# Adafruit_0_96in_160x80_TFT_Display.net
KiCad netlist of a schematic drawn in EAGLE
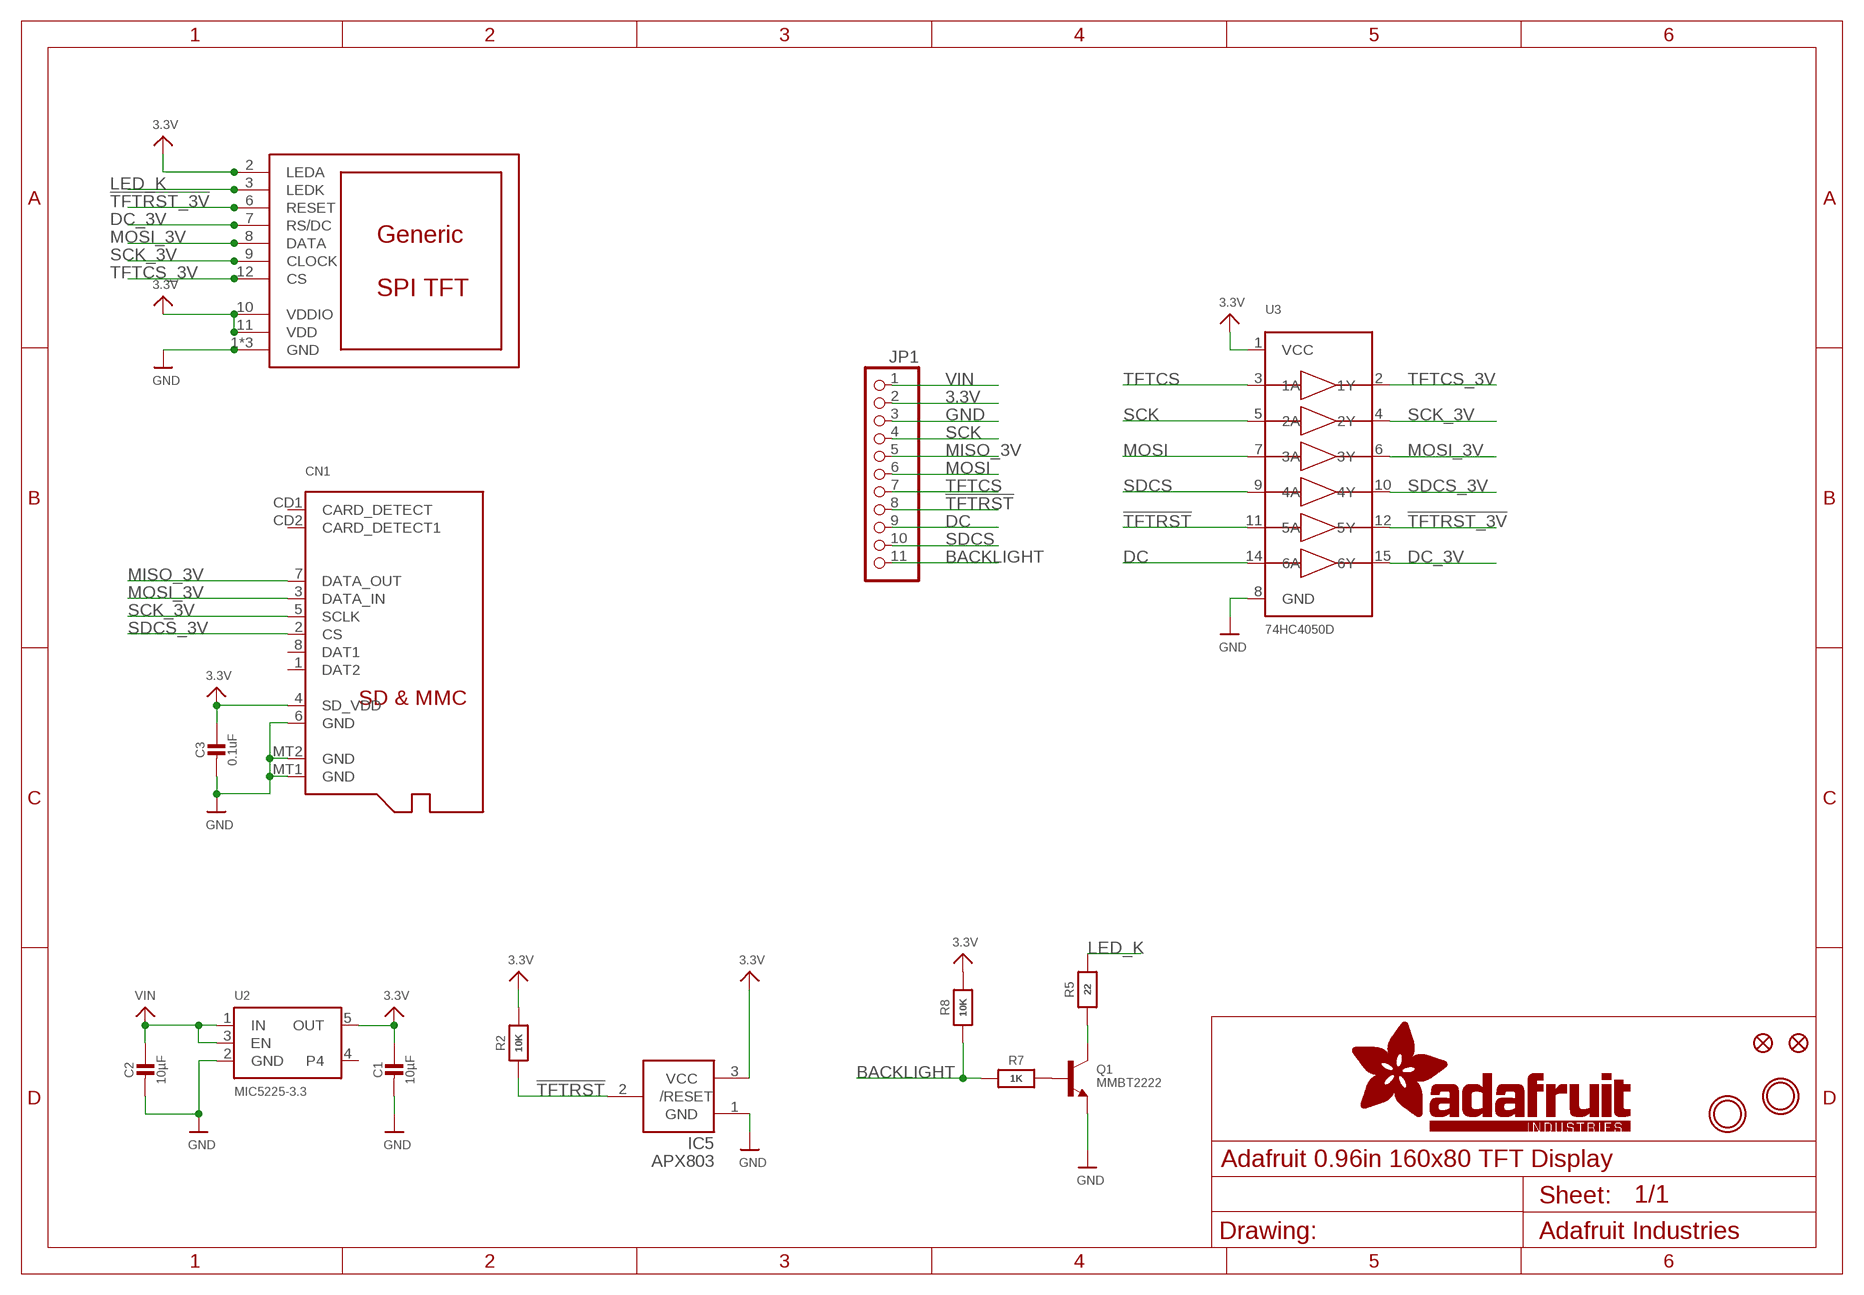
[diagram p0: schematic, sheet 1]

(export (version "E")
  (design (tool "Eeschema 10.0.6"))
  (components
    (comp (ref "C1")
      (value "10µF")
      (footprint "eagle-import:0805-NO")
      (libsource (lib "eagle-import") (part "CAP_CERAMIC0805-NOOUTLINE"))
    )
    (comp (ref "C2")
      (value "10µF")
      (footprint "eagle-import:0805-NO")
      (libsource (lib "eagle-import") (part "CAP_CERAMIC0805-NOOUTLINE"))
    )
    (comp (ref "C3")
      (value "0.1uF")
      (footprint "eagle-import:0805-NO")
      (libsource (lib "eagle-import") (part "CAP_CERAMIC0805-NOOUTLINE"))
    )
    (comp (ref "CN1")
      (value "MICROSD")
      (footprint "eagle-import:MICROSD")
      (libsource (lib "eagle-import") (part "MICROSD"))
    )
    (comp (ref "FID1")
      (value "FIDUCIAL_1MM")
      (footprint "eagle-import:FIDUCIAL_1MM")
      (libsource (lib "eagle-import") (part "FIDUCIAL_1MM"))
    )
    (comp (ref "FID2")
      (value "FIDUCIAL_1MM")
      (footprint "eagle-import:FIDUCIAL_1MM")
      (libsource (lib "eagle-import") (part "FIDUCIAL_1MM"))
    )
    (comp (ref "IC5")
      (value "APX803")
      (footprint "eagle-import:SOT23")
      (libsource (lib "eagle-import") (part "AXP083-SAG"))
    )
    (comp (ref "JP1")
      (value "HEADER-1X11")
      (footprint "eagle-import:1X11_ROUND")
      (libsource (lib "eagle-import") (part "HEADER-1X11"))
    )
    (comp (ref "Q1")
      (value "MMBT2222")
      (footprint "eagle-import:SOT23-WIDE")
      (libsource (lib "eagle-import") (part "TRANSISTOR_NPNWIDE"))
    )
    (comp (ref "R2")
      (value "10K")
      (footprint "eagle-import:0603-NO")
      (libsource (lib "eagle-import") (part "RESISTOR_0603_NOOUT"))
    )
    (comp (ref "R5")
      (value "22")
      (footprint "eagle-import:0603-NO")
      (libsource (lib "eagle-import") (part "RESISTOR_0603_NOOUT"))
    )
    (comp (ref "R7")
      (value "1K")
      (footprint "eagle-import:0603-NO")
      (libsource (lib "eagle-import") (part "RESISTOR_0603_NOOUT"))
    )
    (comp (ref "R8")
      (value "10K")
      (footprint "eagle-import:0603-NO")
      (libsource (lib "eagle-import") (part "RESISTOR_0603_NOOUT"))
    )
    (comp (ref "U$2")
      (value "DISP_LCD_0.9IN_160X80")
      (footprint "eagle-import:TFT_0.96IN_160X80")
      (libsource (lib "eagle-import") (part "DISP_LCD_0.9IN_160X80"))
    )
    (comp (ref "U$9")
      (value "MOUNTINGHOLE2.5")
      (footprint "eagle-import:MOUNTINGHOLE_2.5_PLATED")
      (libsource (lib "eagle-import") (part "MOUNTINGHOLE2.5"))
    )
    (comp (ref "U$10")
      (value "MOUNTINGHOLE2.5")
      (footprint "eagle-import:MOUNTINGHOLE_2.5_PLATED")
      (libsource (lib "eagle-import") (part "MOUNTINGHOLE2.5"))
    )
    (comp (ref "U2")
      (value "MIC5225-3.3")
      (footprint "eagle-import:SOT23-5")
      (libsource (lib "eagle-import") (part "VREG_SOT23-5"))
    )
    (comp (ref "U3")
      (value "74HC4050D")
      (footprint "eagle-import:SOIC16")
      (libsource (lib "eagle-import") (part "74HC4050D"))
    )
  )
  (nets
    (net (code "1") (name "/BACKLIGHT") (class "Default")
      (node (ref "JP1") (pin "11") (pinfunction "11_11") (pintype "passive"))
      (node (ref "R7") (pin "1") (pinfunction "1_1") (pintype "passive"))
      (node (ref "R8") (pin "1") (pinfunction "1_1") (pintype "passive"))
    )
    (net (code "2") (name "/DC") (class "Default")
      (node (ref "JP1") (pin "9") (pinfunction "9_9") (pintype "passive"))
      (node (ref "U3") (pin "14") (pinfunction "6A_14") (pintype "bidirectional"))
    )
    (net (code "3") (name "/DC_3V") (class "Default")
      (node (ref "U$2") (pin "7") (pinfunction "RS/DC_7") (pintype "input"))
      (node (ref "U3") (pin "15") (pinfunction "6Y_15") (pintype "bidirectional"))
    )
    (net (code "4") (name "/LED_K") (class "Default")
      (node (ref "R5") (pin "2") (pinfunction "2_2") (pintype "passive"))
      (node (ref "U$2") (pin "3") (pinfunction "LEDK_3") (pintype "input"))
    )
    (net (code "5") (name "/MISO_3V") (class "Default")
      (node (ref "CN1") (pin "7") (pinfunction "DATA_OUT_7") (pintype "output"))
      (node (ref "JP1") (pin "5") (pinfunction "5_5") (pintype "passive"))
    )
    (net (code "6") (name "/MOSI") (class "Default")
      (node (ref "JP1") (pin "6") (pinfunction "6_6") (pintype "passive"))
      (node (ref "U3") (pin "7") (pinfunction "3A_7") (pintype "bidirectional"))
    )
    (net (code "7") (name "/MOSI_3V") (class "Default")
      (node (ref "CN1") (pin "3") (pinfunction "DATA_IN_3") (pintype "input"))
      (node (ref "U$2") (pin "8") (pinfunction "DATA_8") (pintype "bidirectional"))
      (node (ref "U3") (pin "6") (pinfunction "3Y_6") (pintype "bidirectional"))
    )
    (net (code "8") (name "/SCK") (class "Default")
      (node (ref "JP1") (pin "4") (pinfunction "4_4") (pintype "passive"))
      (node (ref "U3") (pin "5") (pinfunction "2A_5") (pintype "bidirectional"))
    )
    (net (code "9") (name "/SCK_3V") (class "Default")
      (node (ref "CN1") (pin "5") (pinfunction "SCLK_5") (pintype "input"))
      (node (ref "U$2") (pin "9") (pinfunction "CLOCK_9") (pintype "input"))
      (node (ref "U3") (pin "4") (pinfunction "2Y_4") (pintype "bidirectional"))
    )
    (net (code "10") (name "/SDCS") (class "Default")
      (node (ref "JP1") (pin "10") (pinfunction "10_10") (pintype "passive"))
      (node (ref "U3") (pin "9") (pinfunction "4A_9") (pintype "bidirectional"))
    )
    (net (code "11") (name "/SDCS_3V") (class "Default")
      (node (ref "CN1") (pin "2") (pinfunction "CS_2") (pintype "input"))
      (node (ref "U3") (pin "10") (pinfunction "4Y_10") (pintype "bidirectional"))
    )
    (net (code "12") (name "/TFTCS") (class "Default")
      (node (ref "JP1") (pin "7") (pinfunction "7_7") (pintype "passive"))
      (node (ref "U3") (pin "3") (pinfunction "1A_3") (pintype "bidirectional"))
    )
    (net (code "13") (name "/TFTCS_3V") (class "Default")
      (node (ref "U$2") (pin "12") (pinfunction "CS_12") (pintype "input"))
      (node (ref "U3") (pin "2") (pinfunction "1Y_2") (pintype "bidirectional"))
    )
    (net (code "14") (name "/~{TFTRST_3V}") (class "Default")
      (node (ref "U$2") (pin "6") (pinfunction "RESET_6") (pintype "input"))
      (node (ref "U3") (pin "12") (pinfunction "5Y_12") (pintype "bidirectional"))
    )
    (net (code "15") (name "/~{TFTRST}") (class "Default")
      (node (ref "IC5") (pin "2") (pinfunction "/RESET_2") (pintype "output"))
      (node (ref "JP1") (pin "8") (pinfunction "8_8") (pintype "passive"))
      (node (ref "R2") (pin "1") (pinfunction "1_1") (pintype "passive"))
      (node (ref "U3") (pin "11") (pinfunction "5A_11") (pintype "bidirectional"))
    )
    (net (code "16") (name "3.3V") (class "Default")
      (node (ref "C1") (pin "1") (pinfunction "1_1") (pintype "passive"))
      (node (ref "C3") (pin "1") (pinfunction "1_1") (pintype "passive"))
      (node (ref "CN1") (pin "4") (pinfunction "SD_VDD_4") (pintype "power_in"))
      (node (ref "IC5") (pin "3") (pinfunction "VCC_3") (pintype "power_in"))
      (node (ref "JP1") (pin "2") (pinfunction "2_2") (pintype "passive"))
      (node (ref "R2") (pin "2") (pinfunction "2_2") (pintype "passive"))
      (node (ref "R8") (pin "2") (pinfunction "2_2") (pintype "passive"))
      (node (ref "U$2") (pin "10") (pinfunction "VDDIO_10") (pintype "power_in"))
      (node (ref "U$2") (pin "11") (pinfunction "VDD_11") (pintype "power_in"))
      (node (ref "U$2") (pin "2") (pinfunction "LEDA_2") (pintype "input"))
      (node (ref "U2") (pin "5") (pinfunction "OUT_5") (pintype "power_in"))
      (node (ref "U3") (pin "1") (pinfunction "VCC_1") (pintype "bidirectional"))
    )
    (net (code "17") (name "GND") (class "Default")
      (node (ref "C1") (pin "2") (pinfunction "2_2") (pintype "passive"))
      (node (ref "C2") (pin "2") (pinfunction "2_2") (pintype "passive"))
      (node (ref "C3") (pin "2") (pinfunction "2_2") (pintype "passive"))
      (node (ref "CN1") (pin "6") (pinfunction "GND_6") (pintype "power_in"))
      (node (ref "CN1") (pin "MT1") (pinfunction "GND_MT1") (pintype "power_in"))
      (node (ref "CN1") (pin "MT2") (pinfunction "GND_MT2") (pintype "power_in"))
      (node (ref "IC5") (pin "1") (pinfunction "GND_1") (pintype "power_in"))
      (node (ref "JP1") (pin "3") (pinfunction "3_3") (pintype "passive"))
      (node (ref "Q1") (pin "2") (pinfunction "E_2") (pintype "passive"))
      (node (ref "U$2") (pin "1") (pinfunction "GND_1") (pintype "power_in"))
      (node (ref "U$2") (pin "13") (pinfunction "GND_13") (pintype "power_in"))
      (node (ref "U$2") (pin "5") (pinfunction "GND_5") (pintype "power_in"))
      (node (ref "U2") (pin "2") (pinfunction "GND_2") (pintype "power_in"))
      (node (ref "U3") (pin "8") (pinfunction "GND_8") (pintype "bidirectional"))
    )
    (net (code "18") (name "Net-(Q1-B)") (class "Default")
      (node (ref "Q1") (pin "1") (pinfunction "B_1") (pintype "passive"))
      (node (ref "R7") (pin "2") (pinfunction "2_2") (pintype "passive"))
    )
    (net (code "19") (name "Net-(Q1-C)") (class "Default")
      (node (ref "Q1") (pin "3") (pinfunction "C_3") (pintype "passive"))
      (node (ref "R5") (pin "1") (pinfunction "1_1") (pintype "passive"))
    )
    (net (code "20") (name "VIN") (class "Default")
      (node (ref "C2") (pin "1") (pinfunction "1_1") (pintype "passive"))
      (node (ref "JP1") (pin "1") (pinfunction "1_1") (pintype "passive"))
      (node (ref "U2") (pin "1") (pinfunction "IN_1") (pintype "power_in"))
      (node (ref "U2") (pin "3") (pinfunction "EN_3") (pintype "input"))
    )
    (net (code "21") (name "unconnected-(CN1-CARD_DETECT-PadCD1)") (class "Default")
      (node (ref "CN1") (pin "CD1") (pinfunction "CARD_DETECT_CD1") (pintype "passive"))
    )
    (net (code "22") (name "unconnected-(CN1-CARD_DETECT1-PadCD2)") (class "Default")
      (node (ref "CN1") (pin "CD2") (pinfunction "CARD_DETECT1_CD2") (pintype "passive"))
    )
    (net (code "23") (name "unconnected-(CN1-DAT1-Pad8)") (class "Default")
      (node (ref "CN1") (pin "8") (pinfunction "DAT1_8") (pintype "bidirectional"))
    )
    (net (code "24") (name "unconnected-(CN1-DAT2-Pad1)") (class "Default")
      (node (ref "CN1") (pin "1") (pinfunction "DAT2_1") (pintype "bidirectional"))
    )
    (net (code "25") (name "unconnected-(U2-P4-Pad4)") (class "Default")
      (node (ref "U2") (pin "4") (pinfunction "P4_4") (pintype "bidirectional"))
    )
  )
)
